# CPU.net
KiCad netlist of a schematic drawn in Altium Designer
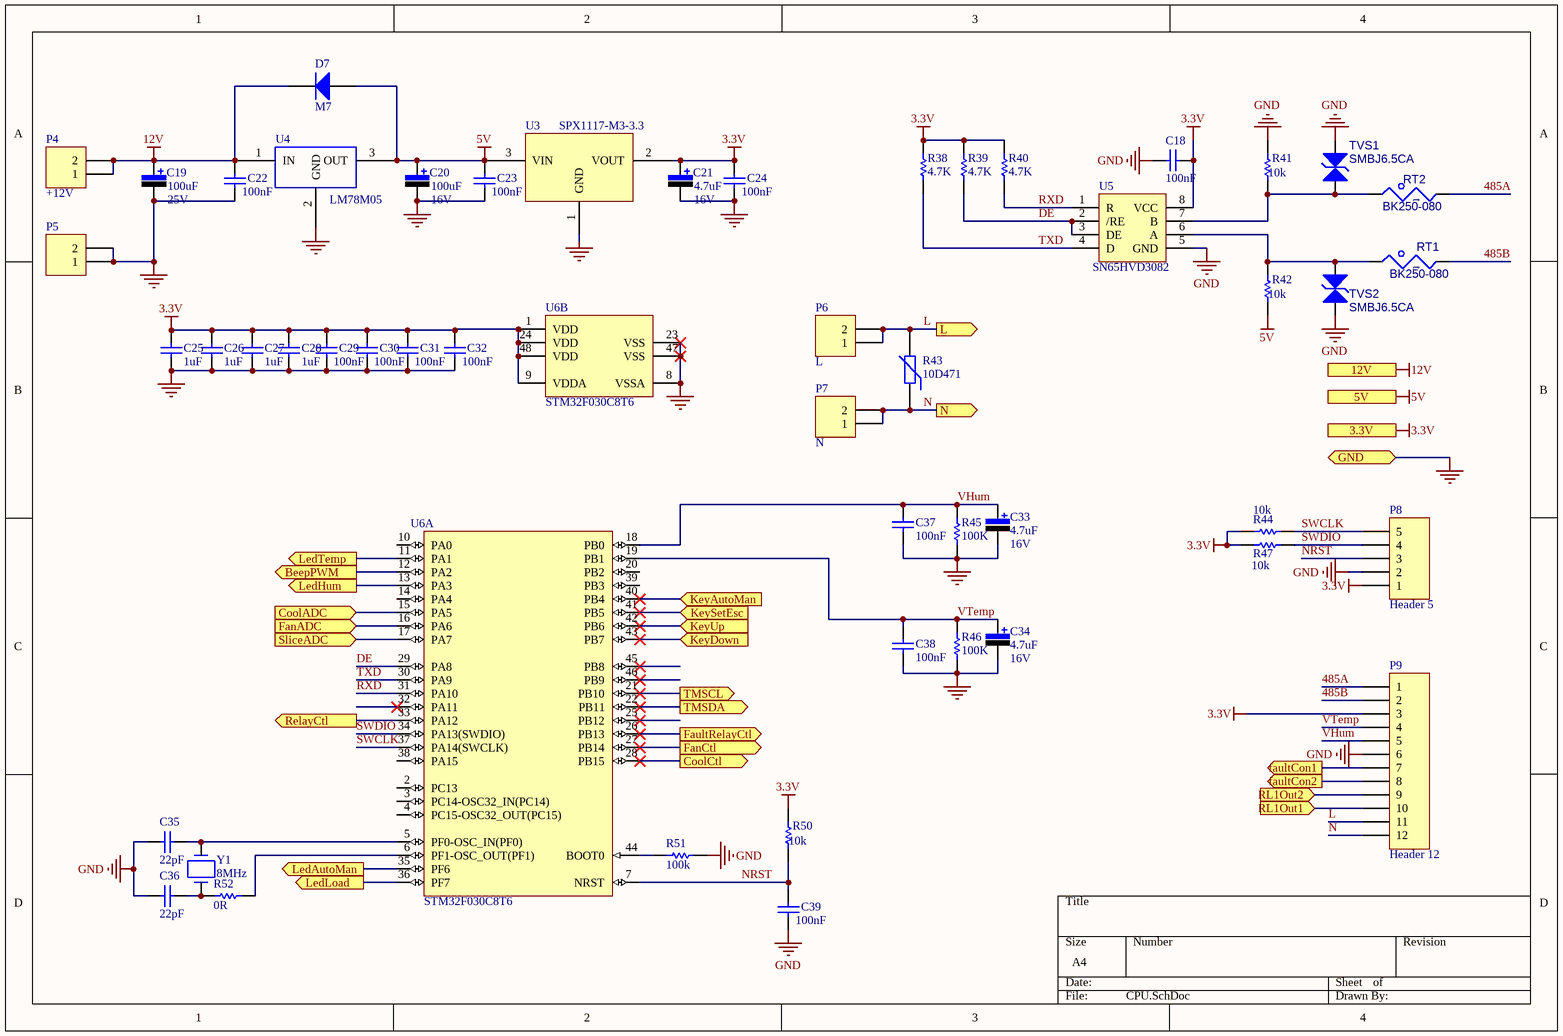
[diagram p0: CPU.SchDoc]

(export (version "E")
  (design (tool "Eeschema 10.0.6"))
  (components
    (comp (ref "C18")
      (value "100nF (104) 10% 50V")
      (footprint "0603_C")
      (description "贴片电容")
      (fields (field (name "ALTIUM_UNNAMED_1") "100nF"))
      (libsource (lib "Miscellaneous Devices LC") (part "0603 100nF (104) 10% 50V"))
    )
    (comp (ref "C19")
      (value "100uF")
      (footprint "C-RB-8")
      (description "100uF/25V")
      (fields (field (name "VOL") "25V") (field (name "PUBLISHER") "Altium Limited"))
      (libsource (lib "fszhang") (part "Cap Pol"))
    )
    (comp (ref "C20")
      (value "100uF")
      (footprint "C-RB-8")
      (description "100uF/16V")
      (fields (field (name "VOL") "16V") (field (name "PUBLISHER") "Altium Limited"))
      (libsource (lib "fszhang") (part "Cap Pol"))
    )
    (comp (ref "C21")
      (value "4.7uF")
      (footprint "CAP-1206")
      (description "4.7uF/16V钽电容")
      (fields
        (field (name "VOL") "16V")
        (field (name "Comment") "4.7uF/16V")
        (field (name "PUBLISHER") "Altium Limited")
      )
      (libsource (lib "fszhang") (part "Cap Pol"))
    )
    (comp (ref "C22")
      (value "100nF (104) 10% 50V")
      (footprint "0603_C")
      (description "贴片电容")
      (fields (field (name "ALTIUM_UNNAMED_1") "100nF"))
      (libsource (lib "Miscellaneous Devices LC") (part "0603 100nF (104) 10% 50V"))
    )
    (comp (ref "C23")
      (value "100nF (104) 10% 50V")
      (footprint "0603_C")
      (description "贴片电容")
      (fields (field (name "ALTIUM_UNNAMED_1") "100nF"))
      (libsource (lib "Miscellaneous Devices LC") (part "0603 100nF (104) 10% 50V"))
    )
    (comp (ref "C24")
      (value "100nF (104) 10% 50V")
      (footprint "0603_C")
      (description "贴片电容")
      (fields (field (name "ALTIUM_UNNAMED_1") "100nF"))
      (libsource (lib "Miscellaneous Devices LC") (part "0603 100nF (104) 10% 50V"))
    )
    (comp (ref "C25")
      (value "1uF (105) 10% 50V")
      (footprint "0603_C")
      (description "贴片电容")
      (fields (field (name "ALTIUM_UNNAMED_1") "1uF"))
      (libsource (lib "Miscellaneous Devices LC") (part "0603 1uF (105) 10% 50V"))
    )
    (comp (ref "C26")
      (value "1uF (105) 10% 50V")
      (footprint "0603_C")
      (description "贴片电容")
      (fields (field (name "ALTIUM_UNNAMED_1") "1uF"))
      (libsource (lib "Miscellaneous Devices LC") (part "0603 1uF (105) 10% 50V"))
    )
    (comp (ref "C27")
      (value "1uF (105) 10% 50V")
      (footprint "0603_C")
      (description "贴片电容")
      (fields (field (name "ALTIUM_UNNAMED_1") "1uF"))
      (libsource (lib "Miscellaneous Devices LC") (part "0603 1uF (105) 10% 50V"))
    )
    (comp (ref "C28")
      (value "1uF (105) 10% 50V")
      (footprint "0603_C")
      (description "贴片电容")
      (fields (field (name "ALTIUM_UNNAMED_1") "1uF"))
      (libsource (lib "Miscellaneous Devices LC") (part "0603 1uF (105) 10% 50V"))
    )
    (comp (ref "C29")
      (value "100nF (104) 10% 50V")
      (footprint "0603_C")
      (description "贴片电容")
      (fields (field (name "ALTIUM_UNNAMED_1") "100nF"))
      (libsource (lib "Miscellaneous Devices LC") (part "0603 100nF (104) 10% 50V"))
    )
    (comp (ref "C30")
      (value "100nF (104) 10% 50V")
      (footprint "0603_C")
      (description "贴片电容")
      (fields (field (name "ALTIUM_UNNAMED_1") "100nF"))
      (libsource (lib "Miscellaneous Devices LC") (part "0603 100nF (104) 10% 50V"))
    )
    (comp (ref "C31")
      (value "100nF (104) 10% 50V")
      (footprint "0603_C")
      (description "贴片电容")
      (fields (field (name "ALTIUM_UNNAMED_1") "100nF"))
      (libsource (lib "Miscellaneous Devices LC") (part "0603 100nF (104) 10% 50V"))
    )
    (comp (ref "C32")
      (value "100nF (104) 10% 50V")
      (footprint "0603_C")
      (description "贴片电容")
      (fields (field (name "ALTIUM_UNNAMED_1") "100nF"))
      (libsource (lib "Miscellaneous Devices LC") (part "0603 100nF (104) 10% 50V"))
    )
    (comp (ref "C33")
      (value "4.7uF")
      (footprint "CAP-1206")
      (description "4.7uF/16V钽电容")
      (fields
        (field (name "VOL") "16V")
        (field (name "Comment") "4.7uF/16V")
        (field (name "PUBLISHER") "Altium Limited")
      )
      (libsource (lib "fszhang") (part "Cap Pol"))
    )
    (comp (ref "C34")
      (value "4.7uF")
      (footprint "CAP-1206")
      (description "4.7uF/16V钽电容")
      (fields
        (field (name "VOL") "16V")
        (field (name "Comment") "4.7uF/16V")
        (field (name "PUBLISHER") "Altium Limited")
      )
      (libsource (lib "fszhang") (part "Cap Pol"))
    )
    (comp (ref "C35")
      (value "22pF (220) 5% 50V")
      (footprint "0603_C")
      (description "贴片电容")
      (fields (field (name "ALTIUM_UNNAMED_1") "22pF"))
      (libsource (lib "Miscellaneous Devices LC") (part "0603 22pF (220) 5% 50V"))
    )
    (comp (ref "C36")
      (value "22pF (220) 5% 50V")
      (footprint "0603_C")
      (description "贴片电容")
      (fields (field (name "ALTIUM_UNNAMED_1") "22pF"))
      (libsource (lib "Miscellaneous Devices LC") (part "0603 22pF (220) 5% 50V"))
    )
    (comp (ref "C37")
      (value "100nF (104) 10% 50V")
      (footprint "0603_C")
      (description "贴片电容")
      (fields (field (name "ALTIUM_UNNAMED_1") "100nF"))
      (libsource (lib "Miscellaneous Devices LC") (part "0603 100nF (104) 10% 50V"))
    )
    (comp (ref "C38")
      (value "100nF (104) 10% 50V")
      (footprint "0603_C")
      (description "贴片电容")
      (fields (field (name "ALTIUM_UNNAMED_1") "100nF"))
      (libsource (lib "Miscellaneous Devices LC") (part "0603 100nF (104) 10% 50V"))
    )
    (comp (ref "C39")
      (value "100nF (104) 10% 50V")
      (footprint "0603_C")
      (description "贴片电容")
      (fields (field (name "ALTIUM_UNNAMED_1") "100nF"))
      (libsource (lib "Miscellaneous Devices LC") (part "0603 100nF (104) 10% 50V"))
    )
    (comp (ref "D7")
      (value "M7")
      (footprint "DO214AC-SMA")
      (description "二极管")
      (fields (field (name "PUBLISHER") "Altium Limited"))
      (libsource (lib "Fszhang") (part "Diode"))
    )
    (comp (ref "P4")
      (value "+12V")
      (footprint "ConSlice0.5")
      (description "Header, 2-Pin")
      (fields (field (name "PUBLISHER") "Altium Limited"))
      (libsource (lib "Miscellaneous Connectors") (part "Header 2"))
    )
    (comp (ref "P5")
      (value "~")
      (footprint "ConSlice0.5")
      (description "Header, 2-Pin")
      (fields (field (name "PUBLISHER") "Altium Limited"))
      (libsource (lib "Miscellaneous Connectors") (part "Header 2"))
    )
    (comp (ref "P6")
      (value "L")
      (footprint "ConSlice0.5")
      (description "Header, 2-Pin")
      (fields (field (name "PUBLISHER") "Altium Limited"))
      (libsource (lib "Miscellaneous Connectors") (part "Header 2"))
    )
    (comp (ref "P7")
      (value "N")
      (footprint "ConSlice0.5")
      (description "Header, 2-Pin")
      (fields (field (name "PUBLISHER") "Altium Limited"))
      (libsource (lib "Miscellaneous Connectors") (part "Header 2"))
    )
    (comp (ref "P8")
      (value "Header 5")
      (footprint "HDR1X5")
      (description "Header, 5-Pin")
      (fields (field (name "PUBLISHER") "Altium Limited"))
      (libsource (lib "Miscellaneous Connectors") (part "Header 5"))
    )
    (comp (ref "P9")
      (value "Header 12")
      (footprint "HDR3.5-12P_1")
      (description "Header, 12-Pin")
      (fields (field (name "PUBLISHER") "Altium Limited"))
      (libsource (lib "Miscellaneous Connectors") (part "Header 12"))
    )
    (comp (ref "R38")
      (value "4.7K")
      (footprint "RESC1608N-R0603")
      (description "4.7K/±10%")
      (libsource (lib "Free Documents") (part "RES1"))
    )
    (comp (ref "R39")
      (value "4.7K")
      (footprint "RESC1608N-R0603")
      (description "4.7K/±10%")
      (libsource (lib "Free Documents") (part "RES1"))
    )
    (comp (ref "R40")
      (value "4.7K")
      (footprint "RESC1608N-R0603")
      (description "4.7K/±10%")
      (libsource (lib "Free Documents") (part "RES1"))
    )
    (comp (ref "R41")
      (value "10k")
      (footprint "RESC1608N-R0603")
      (description "10k/±10%")
      (libsource (lib "Free Documents") (part "RES1"))
    )
    (comp (ref "R42")
      (value "10k")
      (footprint "RESC1608N-R0603")
      (description "10k/±10%")
      (libsource (lib "Free Documents") (part "RES1"))
    )
    (comp (ref "R43")
      (value "10D471")
      (footprint "10D471K")
      (description "Varistor (Voltage-Sensitive Resistor)")
      (fields (field (name "PUBLISHER") "Altium Limited"))
      (libsource (lib "LifeTestDevice") (part "Res Varistor"))
    )
    (comp (ref "R44")
      (value "10k")
      (footprint "RESC1608N-R0603")
      (description "10k/±10%")
      (libsource (lib "Free Documents") (part "RES1"))
    )
    (comp (ref "R45")
      (value "100K")
      (footprint "RESC1608N-R0603")
      (description "100K/±10%")
      (libsource (lib "Free Documents") (part "RES1"))
    )
    (comp (ref "R46")
      (value "100K")
      (footprint "RESC1608N-R0603")
      (description "100K/±10%")
      (libsource (lib "Free Documents") (part "RES1"))
    )
    (comp (ref "R47")
      (value "10k")
      (footprint "RESC1608N-R0603")
      (description "10k/±10%")
      (libsource (lib "Free Documents") (part "RES1"))
    )
    (comp (ref "R50")
      (value "10k")
      (footprint "RESC1608N-R0603")
      (description "10k/±10%")
      (libsource (lib "Free Documents") (part "RES1"))
    )
    (comp (ref "R51")
      (value "100k")
      (footprint "RESC1608N-R0603")
      (description "100K/±10%")
      (libsource (lib "Free Documents") (part "RES1"))
    )
    (comp (ref "R52")
      (value "0R")
      (footprint "RESC1608N-R0603")
      (description "0R±10%")
      (libsource (lib "Free Documents") (part "RES1"))
    )
    (comp (ref "RT1")
      (value "BK250-080")
      (footprint "RAD0.2")
      (description "热敏电阻")
      (libsource (lib "CET_SchLib_CommonV1.0_111129") (part "PTC-Thermistor"))
    )
    (comp (ref "RT2")
      (value "BK250-080")
      (footprint "RAD0.2")
      (description "热敏电阻")
      (libsource (lib "CET_SchLib_CommonV1.0_111129") (part "PTC-Thermistor"))
    )
    (comp (ref "TVS1")
      (value "SMBJ6.5CA")
      (footprint "1812")
      (description "TVS")
      (libsource (lib "CET_SchLib_CommonV1.0_111129") (part "TVS管-贴片"))
    )
    (comp (ref "TVS2")
      (value "SMBJ6.5CA")
      (footprint "1812")
      (description "TVS")
      (libsource (lib "CET_SchLib_CommonV1.0_111129") (part "TVS管-贴片"))
    )
    (comp (ref "U3")
      (value "SPX1117-M3-3.3")
      (footprint "SOT223")
      (libsource (lib "BPD-REV1") (part "IC-SPX1117M3-L-3.3 工业级 SOT-223 SIPEX"))
    )
    (comp (ref "U4")
      (value "LM78M05")
      (footprint "DPAK")
      (libsource (lib "2TFE810007D1000 IRTD-CNT board-A") (part "LDO-78XX_1"))
    )
    (comp (ref "U5") (value "SN65HVD3082") (footprint "SO-8") (libsource (lib "*") (part "RS485")))
    (comp (ref "U6")
      (value "STM32F030C8T6")
      (footprint "STM-LQFP48_N")
      (libsource (lib "STMicroelectronics STM32 F0") (part "STM32F030C8T6"))
    )
    (comp (ref "Y1")
      (value "8MHz")
      (footprint "HC49S_th")
      (description "QUARTZ 8MHz SMD")
      (fields (field (name "APPROVED") "MANZOLI R."))
      (libsource (lib "ABB_ALTIUM_Lib") (part "SACE_CRYSTAL"))
    )
  )
  (nets
    (net (code "1") (name "/485A") (class "Default")
      (node (ref "P9") (pin "1") (pinfunction "1_1") (pintype "passive"))
      (node (ref "RT2") (pin "1") (pinfunction "1_1") (pintype "passive"))
    )
    (net (code "2") (name "/485B") (class "Default")
      (node (ref "P9") (pin "2") (pinfunction "2_2") (pintype "passive"))
      (node (ref "RT1") (pin "1") (pinfunction "1_1") (pintype "passive"))
    )
    (net (code "3") (name "/BeepPWM") (class "Default")
      (node (ref "U6") (pin "12") (pinfunction "PA2_12") (pintype "bidirectional"))
    )
    (net (code "4") (name "/CoolADC") (class "Default")
      (node (ref "U6") (pin "15") (pinfunction "PA5_15") (pintype "bidirectional"))
    )
    (net (code "5") (name "/CoolCtl") (class "Default")
      (node (ref "U6") (pin "28") (pinfunction "PB15_28") (pintype "bidirectional+no_connect"))
    )
    (net (code "6") (name "/DE") (class "Default")
      (node (ref "R39") (pin "2") (pinfunction "2_2") (pintype "passive"))
      (node (ref "U5") (pin "2") (pinfunction "/RE_2") (pintype "passive"))
      (node (ref "U5") (pin "3") (pinfunction "DE_3") (pintype "passive"))
      (node (ref "U6") (pin "29") (pinfunction "PA8_29") (pintype "bidirectional"))
    )
    (net (code "7") (name "/FanADC") (class "Default")
      (node (ref "U6") (pin "16") (pinfunction "PA6_16") (pintype "bidirectional"))
    )
    (net (code "8") (name "/FanCtl") (class "Default")
      (node (ref "U6") (pin "27") (pinfunction "PB14_27") (pintype "bidirectional+no_connect"))
    )
    (net (code "9") (name "/FaultRelayCtl") (class "Default")
      (node (ref "U6") (pin "26") (pinfunction "PB13_26") (pintype "bidirectional+no_connect"))
    )
    (net (code "10") (name "/KeyAutoMan") (class "Default")
      (node (ref "U6") (pin "40") (pinfunction "PB4_40") (pintype "bidirectional+no_connect"))
    )
    (net (code "11") (name "/KeyDown") (class "Default")
      (node (ref "U6") (pin "43") (pinfunction "PB7_43") (pintype "bidirectional+no_connect"))
    )
    (net (code "12") (name "/KeySetEsc") (class "Default")
      (node (ref "U6") (pin "41") (pinfunction "PB5_41") (pintype "bidirectional+no_connect"))
    )
    (net (code "13") (name "/KeyUp") (class "Default")
      (node (ref "U6") (pin "42") (pinfunction "PB6_42") (pintype "bidirectional+no_connect"))
    )
    (net (code "14") (name "/L") (class "Default")
      (node (ref "P6") (pin "1") (pinfunction "1_1") (pintype "passive"))
      (node (ref "P6") (pin "2") (pinfunction "2_2") (pintype "passive"))
      (node (ref "P9") (pin "11") (pinfunction "11_11") (pintype "passive"))
      (node (ref "R43") (pin "2") (pinfunction "2_2") (pintype "passive"))
    )
    (net (code "15") (name "/LedAutoMan") (class "Default")
      (node (ref "U6") (pin "35") (pinfunction "PF6_35") (pintype "bidirectional"))
    )
    (net (code "16") (name "/LedHum") (class "Default")
      (node (ref "U6") (pin "13") (pinfunction "PA3_13") (pintype "bidirectional"))
    )
    (net (code "17") (name "/LedLoad") (class "Default")
      (node (ref "U6") (pin "36") (pinfunction "PF7_36") (pintype "bidirectional"))
    )
    (net (code "18") (name "/LedTemp") (class "Default")
      (node (ref "U6") (pin "11") (pinfunction "PA1_11") (pintype "bidirectional"))
    )
    (net (code "19") (name "/N") (class "Default")
      (node (ref "P7") (pin "1") (pinfunction "1_1") (pintype "passive"))
      (node (ref "P7") (pin "2") (pinfunction "2_2") (pintype "passive"))
      (node (ref "P9") (pin "12") (pinfunction "12_12") (pintype "passive"))
      (node (ref "R43") (pin "1") (pinfunction "1_1") (pintype "passive"))
    )
    (net (code "20") (name "/NRST") (class "Default")
      (node (ref "C39") (pin "2") (pinfunction "2_2") (pintype "passive"))
      (node (ref "P8") (pin "3") (pinfunction "3_3") (pintype "passive"))
      (node (ref "R50") (pin "2") (pinfunction "2_2") (pintype "passive"))
      (node (ref "U6") (pin "7") (pinfunction "NRST_7") (pintype "bidirectional"))
    )
    (net (code "21") (name "/RL1Out1") (class "Default")
      (node (ref "P9") (pin "10") (pinfunction "10_10") (pintype "passive"))
    )
    (net (code "22") (name "/RL1Out2") (class "Default")
      (node (ref "P9") (pin "9") (pinfunction "9_9") (pintype "passive"))
    )
    (net (code "23") (name "/RXD") (class "Default")
      (node (ref "R40") (pin "2") (pinfunction "2_2") (pintype "passive"))
      (node (ref "U5") (pin "1") (pinfunction "R_1") (pintype "passive"))
      (node (ref "U6") (pin "31") (pinfunction "PA10_31") (pintype "bidirectional"))
    )
    (net (code "24") (name "/RelayCtl") (class "Default")
      (node (ref "U6") (pin "33") (pinfunction "PA12_33") (pintype "bidirectional"))
    )
    (net (code "25") (name "/SWCLK") (class "Default")
      (node (ref "P8") (pin "5") (pinfunction "5_5") (pintype "passive"))
      (node (ref "R44") (pin "2") (pinfunction "2_2") (pintype "passive"))
      (node (ref "U6") (pin "37") (pinfunction "PA14(SWCLK)_37") (pintype "bidirectional"))
    )
    (net (code "26") (name "/SWDIO") (class "Default")
      (node (ref "P8") (pin "4") (pinfunction "4_4") (pintype "passive"))
      (node (ref "R47") (pin "2") (pinfunction "2_2") (pintype "passive"))
      (node (ref "U6") (pin "34") (pinfunction "PA13(SWDIO)_34") (pintype "bidirectional"))
    )
    (net (code "27") (name "/SliceADC") (class "Default")
      (node (ref "U6") (pin "17") (pinfunction "PA7_17") (pintype "bidirectional"))
    )
    (net (code "28") (name "/TMSCL") (class "Default")
      (node (ref "U6") (pin "21") (pinfunction "PB10_21") (pintype "bidirectional+no_connect"))
    )
    (net (code "29") (name "/TMSDA") (class "Default")
      (node (ref "U6") (pin "22") (pinfunction "PB11_22") (pintype "bidirectional+no_connect"))
    )
    (net (code "30") (name "/TXD") (class "Default")
      (node (ref "R38") (pin "2") (pinfunction "2_2") (pintype "passive"))
      (node (ref "U5") (pin "4") (pinfunction "D_4") (pintype "passive"))
      (node (ref "U6") (pin "30") (pinfunction "PA9_30") (pintype "bidirectional"))
    )
    (net (code "31") (name "/VHum") (class "Default")
      (node (ref "C33") (pin "1") (pinfunction "1_1") (pintype "passive"))
      (node (ref "C37") (pin "2") (pinfunction "2_2") (pintype "passive"))
      (node (ref "P9") (pin "5") (pinfunction "5_5") (pintype "passive"))
      (node (ref "R45") (pin "1") (pinfunction "1_1") (pintype "passive"))
      (node (ref "U6") (pin "18") (pinfunction "PB0_18") (pintype "bidirectional"))
    )
    (net (code "32") (name "/VTemp") (class "Default")
      (node (ref "C34") (pin "1") (pinfunction "1_1") (pintype "passive"))
      (node (ref "C38") (pin "2") (pinfunction "2_2") (pintype "passive"))
      (node (ref "P9") (pin "4") (pinfunction "4_4") (pintype "passive"))
      (node (ref "R46") (pin "1") (pinfunction "1_1") (pintype "passive"))
      (node (ref "U6") (pin "19") (pinfunction "PB1_19") (pintype "bidirectional"))
    )
    (net (code "33") (name "/faultCon1") (class "Default")
      (node (ref "P9") (pin "7") (pinfunction "7_7") (pintype "passive"))
    )
    (net (code "34") (name "/faultCon2") (class "Default")
      (node (ref "P9") (pin "8") (pinfunction "8_8") (pintype "passive"))
    )
    (net (code "35") (name "3.3V") (class "Default")
      (node (ref "C18") (pin "1") (pinfunction "1_1") (pintype "passive"))
      (node (ref "C21") (pin "1") (pinfunction "1_1") (pintype "passive"))
      (node (ref "C24") (pin "2") (pinfunction "2_2") (pintype "passive"))
      (node (ref "C25") (pin "2") (pinfunction "2_2") (pintype "passive"))
      (node (ref "C26") (pin "2") (pinfunction "2_2") (pintype "passive"))
      (node (ref "C27") (pin "2") (pinfunction "2_2") (pintype "passive"))
      (node (ref "C28") (pin "2") (pinfunction "2_2") (pintype "passive"))
      (node (ref "C29") (pin "2") (pinfunction "2_2") (pintype "passive"))
      (node (ref "C30") (pin "2") (pinfunction "2_2") (pintype "passive"))
      (node (ref "C31") (pin "2") (pinfunction "2_2") (pintype "passive"))
      (node (ref "C32") (pin "2") (pinfunction "2_2") (pintype "passive"))
      (node (ref "P8") (pin "1") (pinfunction "1_1") (pintype "passive"))
      (node (ref "P9") (pin "3") (pinfunction "3_3") (pintype "passive"))
      (node (ref "R38") (pin "1") (pinfunction "1_1") (pintype "passive"))
      (node (ref "R39") (pin "1") (pinfunction "1_1") (pintype "passive"))
      (node (ref "R40") (pin "1") (pinfunction "1_1") (pintype "passive"))
      (node (ref "R44") (pin "1") (pinfunction "1_1") (pintype "passive"))
      (node (ref "R47") (pin "1") (pinfunction "1_1") (pintype "passive"))
      (node (ref "R50") (pin "1") (pinfunction "1_1") (pintype "passive"))
      (node (ref "U3") (pin "2") (pinfunction "VOUT_2") (pintype "passive"))
      (node (ref "U5") (pin "8") (pinfunction "VCC_8") (pintype "passive"))
      (node (ref "U6") (pin "1") (pinfunction "VDD_1") (pintype "power_in"))
      (node (ref "U6") (pin "24") (pinfunction "VDD_24") (pintype "power_in"))
      (node (ref "U6") (pin "48") (pinfunction "VDD_48") (pintype "power_in"))
      (node (ref "U6") (pin "9") (pinfunction "VDDA_9") (pintype "power_in"))
    )
    (net (code "36") (name "5V") (class "Default")
      (node (ref "C20") (pin "1") (pinfunction "1_1") (pintype "passive"))
      (node (ref "C23") (pin "2") (pinfunction "2_2") (pintype "passive"))
      (node (ref "D7") (pin "1") (pinfunction "A_1") (pintype "passive"))
      (node (ref "R42") (pin "2") (pinfunction "2_2") (pintype "passive"))
      (node (ref "U3") (pin "3") (pinfunction "VIN_3") (pintype "passive"))
      (node (ref "U4") (pin "3") (pinfunction "OUT_3") (pintype "passive"))
    )
    (net (code "37") (name "12V") (class "Default")
      (node (ref "C19") (pin "1") (pinfunction "1_1") (pintype "passive"))
      (node (ref "C22") (pin "2") (pinfunction "2_2") (pintype "passive"))
      (node (ref "D7") (pin "2") (pinfunction "K_2") (pintype "passive"))
      (node (ref "P4") (pin "1") (pinfunction "1_1") (pintype "passive"))
      (node (ref "P4") (pin "2") (pinfunction "2_2") (pintype "passive"))
      (node (ref "U4") (pin "1") (pinfunction "IN_1") (pintype "passive"))
    )
    (net (code "38") (name "GND") (class "Default")
      (node (ref "C18") (pin "2") (pinfunction "2_2") (pintype "passive"))
      (node (ref "C19") (pin "2") (pinfunction "2_2") (pintype "passive"))
      (node (ref "C20") (pin "2") (pinfunction "2_2") (pintype "passive"))
      (node (ref "C21") (pin "2") (pinfunction "2_2") (pintype "passive"))
      (node (ref "C22") (pin "1") (pinfunction "1_1") (pintype "passive"))
      (node (ref "C23") (pin "1") (pinfunction "1_1") (pintype "passive"))
      (node (ref "C24") (pin "1") (pinfunction "1_1") (pintype "passive"))
      (node (ref "C25") (pin "1") (pinfunction "1_1") (pintype "passive"))
      (node (ref "C26") (pin "1") (pinfunction "1_1") (pintype "passive"))
      (node (ref "C27") (pin "1") (pinfunction "1_1") (pintype "passive"))
      (node (ref "C28") (pin "1") (pinfunction "1_1") (pintype "passive"))
      (node (ref "C29") (pin "1") (pinfunction "1_1") (pintype "passive"))
      (node (ref "C30") (pin "1") (pinfunction "1_1") (pintype "passive"))
      (node (ref "C31") (pin "1") (pinfunction "1_1") (pintype "passive"))
      (node (ref "C32") (pin "1") (pinfunction "1_1") (pintype "passive"))
      (node (ref "C33") (pin "2") (pinfunction "2_2") (pintype "passive"))
      (node (ref "C34") (pin "2") (pinfunction "2_2") (pintype "passive"))
      (node (ref "C35") (pin "2") (pinfunction "2_2") (pintype "passive"))
      (node (ref "C36") (pin "2") (pinfunction "2_2") (pintype "passive"))
      (node (ref "C37") (pin "1") (pinfunction "1_1") (pintype "passive"))
      (node (ref "C38") (pin "1") (pinfunction "1_1") (pintype "passive"))
      (node (ref "C39") (pin "1") (pinfunction "1_1") (pintype "passive"))
      (node (ref "P5") (pin "1") (pinfunction "1_1") (pintype "passive"))
      (node (ref "P5") (pin "2") (pinfunction "2_2") (pintype "passive"))
      (node (ref "P8") (pin "2") (pinfunction "2_2") (pintype "passive"))
      (node (ref "P9") (pin "6") (pinfunction "6_6") (pintype "passive"))
      (node (ref "R41") (pin "1") (pinfunction "1_1") (pintype "passive"))
      (node (ref "R45") (pin "2") (pinfunction "2_2") (pintype "passive"))
      (node (ref "R46") (pin "2") (pinfunction "2_2") (pintype "passive"))
      (node (ref "R51") (pin "2") (pinfunction "2_2") (pintype "passive"))
      (node (ref "TVS1") (pin "1") (pinfunction "A_1") (pintype "passive"))
      (node (ref "TVS2") (pin "2") (pinfunction "K_2") (pintype "passive"))
      (node (ref "U3") (pin "1") (pinfunction "GND_1") (pintype "passive"))
      (node (ref "U4") (pin "2") (pinfunction "GND_2") (pintype "passive"))
      (node (ref "U5") (pin "5") (pinfunction "GND_5") (pintype "passive"))
      (node (ref "U6") (pin "23") (pinfunction "VSS_23") (pintype "power_in"))
      (node (ref "U6") (pin "47") (pinfunction "VSS_47") (pintype "power_in"))
      (node (ref "U6") (pin "8") (pinfunction "VSSA_8") (pintype "power_in"))
    )
    (net (code "39") (name "Net-(C36-Pad1)") (class "Default")
      (node (ref "C36") (pin "1") (pinfunction "1_1") (pintype "passive"))
      (node (ref "R52") (pin "2") (pinfunction "2_2") (pintype "passive"))
      (node (ref "Y1") (pin "2") (pinfunction "2_2") (pintype "passive"))
    )
    (net (code "40") (name "Net-(TVS1-K)") (class "Default")
      (node (ref "R41") (pin "2") (pinfunction "2_2") (pintype "passive"))
      (node (ref "RT2") (pin "2") (pinfunction "2_2") (pintype "passive"))
      (node (ref "TVS1") (pin "2") (pinfunction "K_2") (pintype "passive"))
      (node (ref "U5") (pin "7") (pinfunction "B_7") (pintype "passive"))
    )
    (net (code "41") (name "Net-(TVS2-A)") (class "Default")
      (node (ref "R42") (pin "1") (pinfunction "1_1") (pintype "passive"))
      (node (ref "RT1") (pin "2") (pinfunction "2_2") (pintype "passive"))
      (node (ref "TVS2") (pin "1") (pinfunction "A_1") (pintype "passive"))
      (node (ref "U5") (pin "6") (pinfunction "A_6") (pintype "passive"))
    )
    (net (code "42") (name "Net-(U6A-BOOT0)") (class "Default")
      (node (ref "R51") (pin "1") (pinfunction "1_1") (pintype "passive"))
      (node (ref "U6") (pin "44") (pinfunction "BOOT0_44") (pintype "input"))
    )
    (net (code "43") (name "Net-(U6A-PF0-OSC_IN(PF0))") (class "Default")
      (node (ref "C35") (pin "1") (pinfunction "1_1") (pintype "passive"))
      (node (ref "U6") (pin "5") (pinfunction "PF0-OSC_IN(PF0)_5") (pintype "bidirectional"))
      (node (ref "Y1") (pin "1") (pinfunction "1_1") (pintype "passive"))
    )
    (net (code "44") (name "Net-(U6A-PF1-OSC_OUT(PF1))") (class "Default")
      (node (ref "R52") (pin "1") (pinfunction "1_1") (pintype "passive"))
      (node (ref "U6") (pin "6") (pinfunction "PF1-OSC_OUT(PF1)_6") (pintype "bidirectional"))
    )
    (net (code "45") (name "unconnected-(U6A-PA0-Pad10)") (class "Default")
      (node (ref "U6") (pin "10") (pinfunction "PA0_10") (pintype "bidirectional"))
    )
    (net (code "46") (name "unconnected-(U6A-PA4-Pad14)") (class "Default")
      (node (ref "U6") (pin "14") (pinfunction "PA4_14") (pintype "bidirectional"))
    )
    (net (code "47") (name "unconnected-(U6A-PA11-Pad32)") (class "Default")
      (node (ref "U6") (pin "32") (pinfunction "PA11_32") (pintype "bidirectional+no_connect"))
    )
    (net (code "48") (name "unconnected-(U6A-PA15-Pad38)") (class "Default")
      (node (ref "U6") (pin "38") (pinfunction "PA15_38") (pintype "bidirectional"))
    )
    (net (code "49") (name "unconnected-(U6A-PB2-Pad20)") (class "Default")
      (node (ref "U6") (pin "20") (pinfunction "PB2_20") (pintype "bidirectional"))
    )
    (net (code "50") (name "unconnected-(U6A-PB3-Pad39)") (class "Default")
      (node (ref "U6") (pin "39") (pinfunction "PB3_39") (pintype "bidirectional"))
    )
    (net (code "51") (name "unconnected-(U6A-PB8-Pad45)") (class "Default")
      (node (ref "U6") (pin "45") (pinfunction "PB8_45") (pintype "bidirectional+no_connect"))
    )
    (net (code "52") (name "unconnected-(U6A-PB9-Pad46)") (class "Default")
      (node (ref "U6") (pin "46") (pinfunction "PB9_46") (pintype "bidirectional+no_connect"))
    )
    (net (code "53") (name "unconnected-(U6A-PB12-Pad25)") (class "Default")
      (node (ref "U6") (pin "25") (pinfunction "PB12_25") (pintype "bidirectional+no_connect"))
    )
    (net (code "54") (name "unconnected-(U6A-PC13-Pad2)") (class "Default")
      (node (ref "U6") (pin "2") (pinfunction "PC13_2") (pintype "bidirectional"))
    )
    (net (code "55") (name "unconnected-(U6A-PC14-OSC32_IN(PC14)-Pad3)") (class "Default")
      (node (ref "U6") (pin "3") (pinfunction "PC14-OSC32_IN(PC14)_3") (pintype "bidirectional"))
    )
    (net (code "56") (name "unconnected-(U6A-PC15-OSC32_OUT(PC15)-Pad4)") (class "Default")
      (node (ref "U6") (pin "4") (pinfunction "PC15-OSC32_OUT(PC15)_4") (pintype "bidirectional"))
    )
  )
)
